# KB_Board_schematic.net
KiCad netlist of a schematic drawn in EAGLE
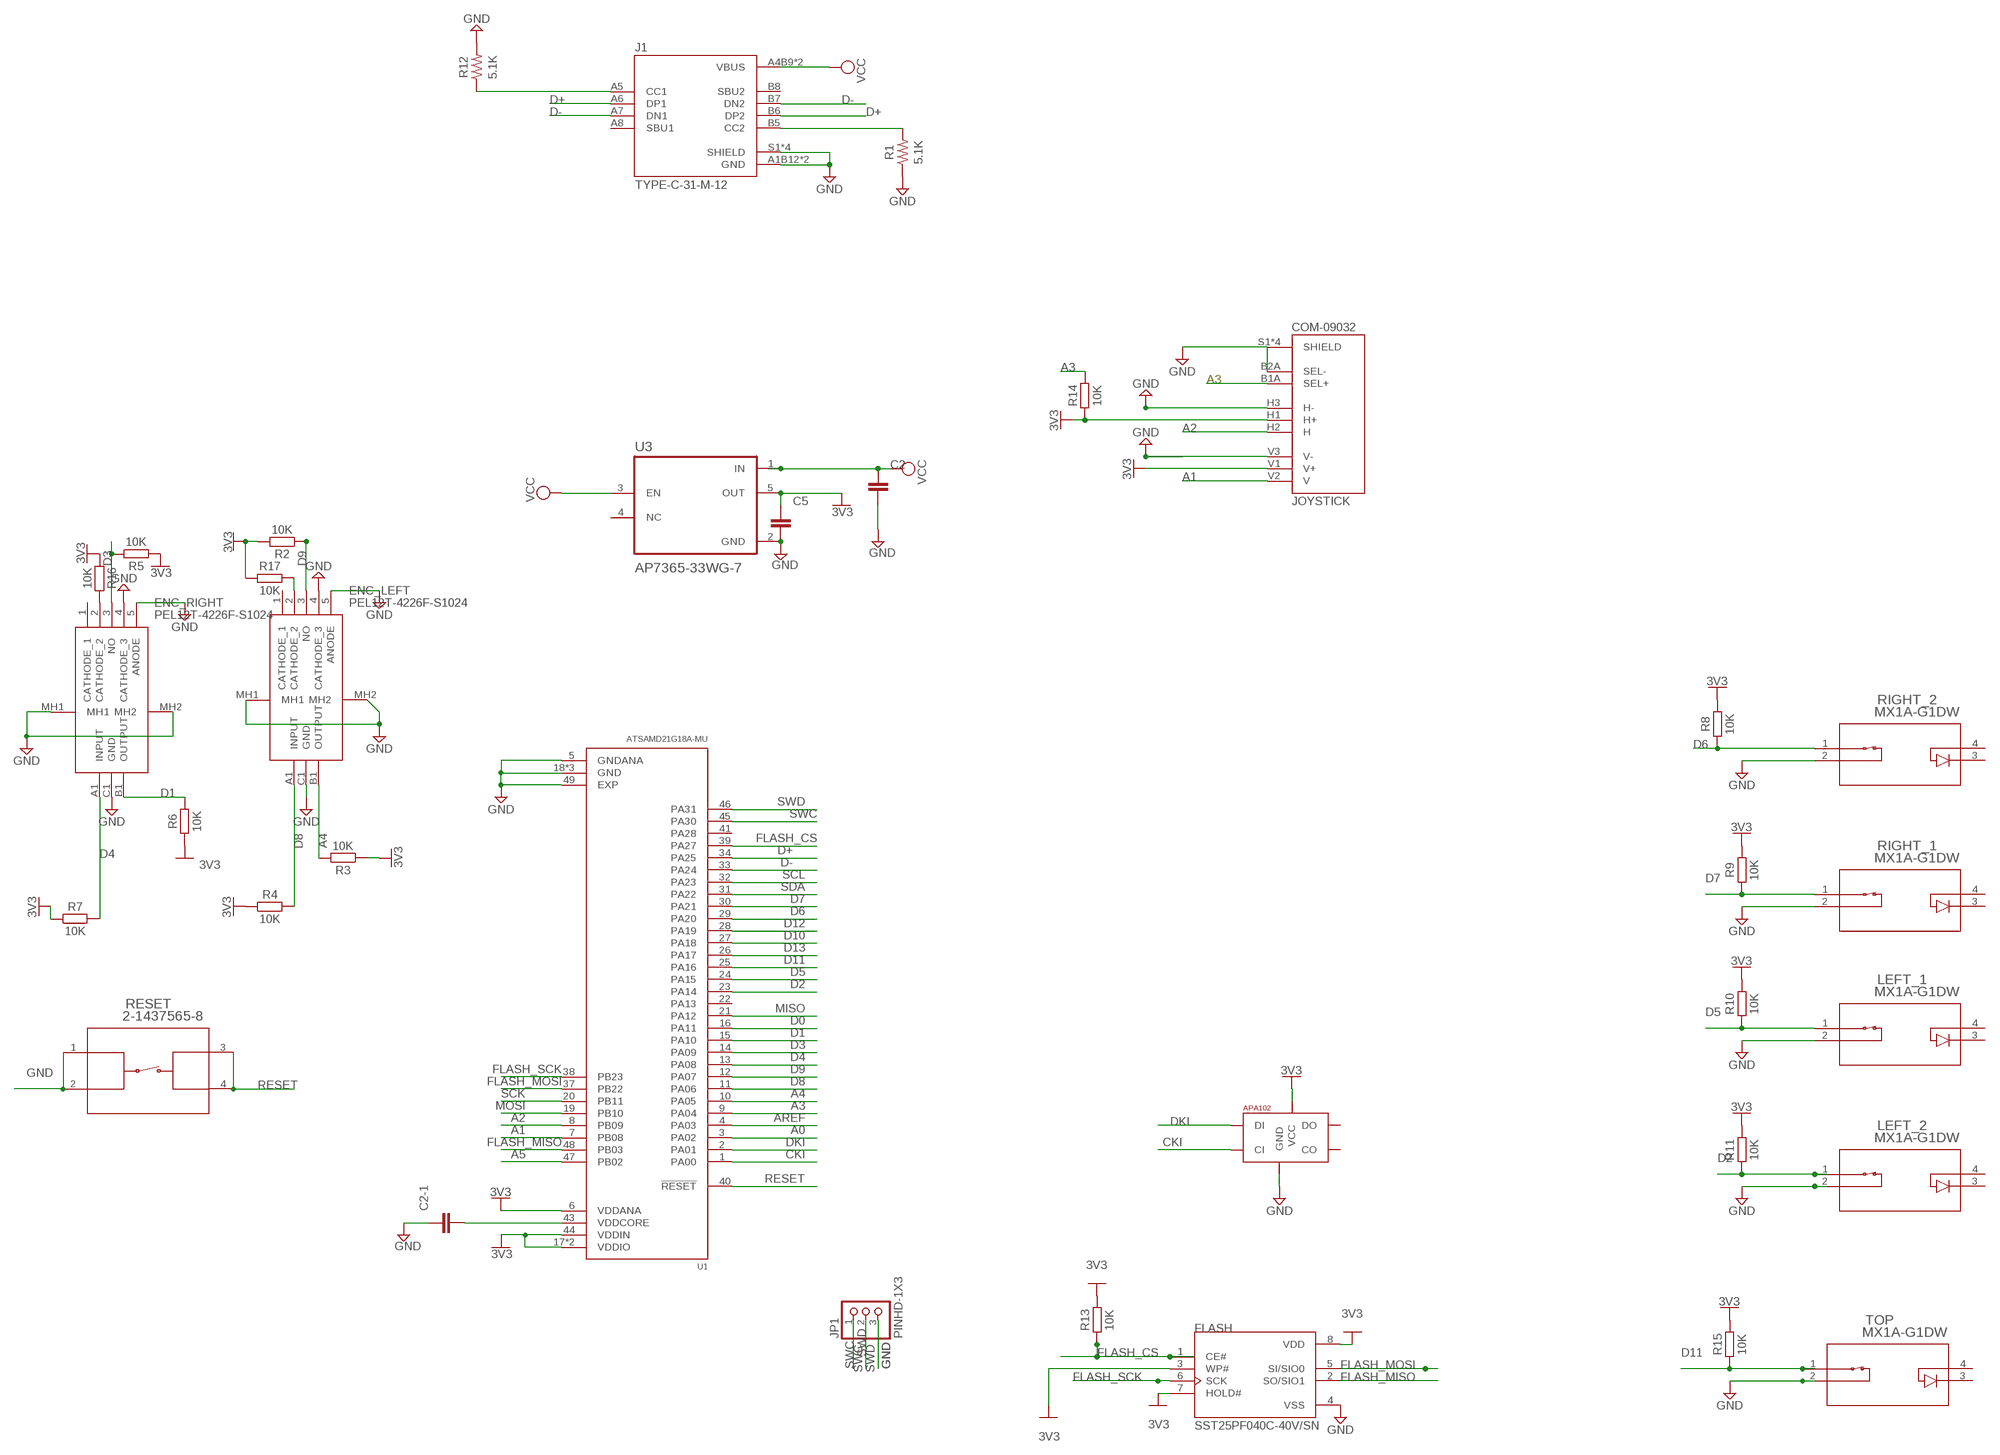
[diagram p0: schematic, sheet 1]

(export (version "E")
  (design (tool "Eeschema 10.0.6"))
  (components
    (comp (ref "C2")
      (value "C_CHIP-0805(2012-METRIC)")
      (footprint "eagle-import:CAPC2012X110")
      (libsource (lib "eagle-import") (part "CCHIP-0805(2012-METRIC)_"))
    )
    (comp (ref "C2-1")
      (value "C_CHIP-0805(2012-METRIC)")
      (footprint "eagle-import:CAPC2012X110")
      (libsource (lib "eagle-import") (part "CCHIP-0805(2012-METRIC)_"))
    )
    (comp (ref "C5")
      (value "C_CHIP-0805(2012-METRIC)")
      (footprint "eagle-import:CAPC2012X110")
      (libsource (lib "eagle-import") (part "CCHIP-0805(2012-METRIC)_"))
    )
    (comp (ref "ENC_LEFT")
      (value "PEL12T-4226F-S1024")
      (footprint "eagle-import:PEL12T4226FS1024")
      (fields (field (name "MOUSER_PART_NUMBER") "652-PEL12T4226FS1024"))
      (libsource (lib "eagle-import") (part "PEL12T-4226F-S1024"))
    )
    (comp (ref "ENC_RIGHT")
      (value "PEL12T-4226F-S1024")
      (footprint "eagle-import:PEL12T4226FS1024")
      (fields (field (name "MOUSER_PART_NUMBER") "652-PEL12T4226FS1024"))
      (libsource (lib "eagle-import") (part "PEL12T-4226F-S1024"))
    )
    (comp (ref "FLASH")
      (value "SST25PF040C-40V/SN")
      (footprint "eagle-import:SOIC8")
      (fields
        (field (name "DIGIKEY_PART_NUMBER") "SST25PF040C-40V/SN-ND")
        (field (name "MANUFACTURER") "Microchip Technology")
        (field (name "CREATED_BY") "PCBLayout.com")
      )
      (libsource (lib "eagle-import") (part "SST25PF040C-40V/SN"))
    )
    (comp (ref "J1")
      (value "TYPE-C-31-M-12")
      (footprint "eagle-import:HRO_TYPE-C-31-M-12")
      (fields (field (name "MANUFACTURER") "HRO Electronics"))
      (libsource (lib "eagle-import") (part "TYPE-C-31-M-12"))
    )
    (comp (ref "JOYSTICK")
      (value "COM-09032")
      (footprint "eagle-import:XDCR_COM-09032")
      (fields (field (name "MANUFACTURER") "SparkFun Electronics"))
      (libsource (lib "eagle-import") (part "COM-09032"))
    )
    (comp (ref "JP1")
      (value "PINHD-1X3")
      (footprint "eagle-import:1X03")
      (libsource (lib "eagle-import") (part "PINHD-1X3"))
    )
    (comp (ref "LEFT_1")
      (value "MX1A-G1DW")
      (footprint "eagle-import:MX1A-G1DW_CHY")
      (fields (field (name "COPYRIGHT") "Copyright (C) 2018 Accelerated Designs. All rights reserved"))
      (libsource (lib "eagle-import") (part "MX1A-G1DW"))
    )
    (comp (ref "LEFT_2")
      (value "MX1A-G1DW")
      (footprint "eagle-import:MX1A-G1DW_CHY")
      (fields (field (name "COPYRIGHT") "Copyright (C) 2018 Accelerated Designs. All rights reserved"))
      (libsource (lib "eagle-import") (part "MX1A-G1DW"))
    )
    (comp (ref "R1")
      (value "5.1K")
      (footprint "eagle-import:RESC1005X40")
      (libsource (lib "eagle-import") (part "R-USCHIP-0402(1005-METRIC)_"))
    )
    (comp (ref "R2")
      (value "10K")
      (footprint "eagle-import:RESC1608X60")
      (libsource (lib "eagle-import") (part "RCHIP-0603(1608-METRIC)_"))
    )
    (comp (ref "R3")
      (value "10K")
      (footprint "eagle-import:RESC1608X60")
      (libsource (lib "eagle-import") (part "RCHIP-0603(1608-METRIC)_"))
    )
    (comp (ref "R4")
      (value "10K")
      (footprint "eagle-import:RESC1608X60")
      (libsource (lib "eagle-import") (part "RCHIP-0603(1608-METRIC)_"))
    )
    (comp (ref "R5")
      (value "10K")
      (footprint "eagle-import:RESC1608X60")
      (libsource (lib "eagle-import") (part "RCHIP-0603(1608-METRIC)_"))
    )
    (comp (ref "R6")
      (value "10K")
      (footprint "eagle-import:RESC1608X60")
      (libsource (lib "eagle-import") (part "RCHIP-0603(1608-METRIC)_"))
    )
    (comp (ref "R7")
      (value "10K")
      (footprint "eagle-import:RESC1608X60")
      (libsource (lib "eagle-import") (part "RCHIP-0603(1608-METRIC)_"))
    )
    (comp (ref "R8")
      (value "10K")
      (footprint "eagle-import:RESC1608X60")
      (libsource (lib "eagle-import") (part "RCHIP-0603(1608-METRIC)_"))
    )
    (comp (ref "R9")
      (value "10K")
      (footprint "eagle-import:RESC1608X60")
      (libsource (lib "eagle-import") (part "RCHIP-0603(1608-METRIC)_"))
    )
    (comp (ref "R10")
      (value "10K")
      (footprint "eagle-import:RESC1608X60")
      (libsource (lib "eagle-import") (part "RCHIP-0603(1608-METRIC)_"))
    )
    (comp (ref "R11")
      (value "10K")
      (footprint "eagle-import:RESC1608X60")
      (libsource (lib "eagle-import") (part "RCHIP-0603(1608-METRIC)_"))
    )
    (comp (ref "R12")
      (value "5.1K")
      (footprint "eagle-import:RESC1005X40")
      (libsource (lib "eagle-import") (part "R-USCHIP-0402(1005-METRIC)_"))
    )
    (comp (ref "R13")
      (value "10K")
      (footprint "eagle-import:RESC1608X60")
      (libsource (lib "eagle-import") (part "RCHIP-0603(1608-METRIC)_"))
    )
    (comp (ref "R14")
      (value "10K")
      (footprint "eagle-import:RESC1608X60")
      (libsource (lib "eagle-import") (part "RCHIP-0603(1608-METRIC)_"))
    )
    (comp (ref "R15")
      (value "10K")
      (footprint "eagle-import:RESC1608X60")
      (libsource (lib "eagle-import") (part "RCHIP-0603(1608-METRIC)_"))
    )
    (comp (ref "R16")
      (value "10K")
      (footprint "eagle-import:RESC1608X60")
      (libsource (lib "eagle-import") (part "RCHIP-0603(1608-METRIC)_"))
    )
    (comp (ref "R17")
      (value "10K")
      (footprint "eagle-import:RESC1608X60")
      (libsource (lib "eagle-import") (part "RCHIP-0603(1608-METRIC)_"))
    )
    (comp (ref "RESET")
      (value "2-1437565-8")
      (footprint "eagle-import:SW4_2-1437565-7")
      (fields (field (name "MANUFACTURER_PART_NUMBER") "FSM2JSMAA"))
      (libsource (lib "eagle-import") (part "2-1437565-8"))
    )
    (comp (ref "RIGHT_1")
      (value "MX1A-G1DW")
      (footprint "eagle-import:MX1A-G1DW_CHY")
      (fields (field (name "COPYRIGHT") "Copyright (C) 2018 Accelerated Designs. All rights reserved"))
      (libsource (lib "eagle-import") (part "MX1A-G1DW"))
    )
    (comp (ref "RIGHT_2")
      (value "MX1A-G1DW")
      (footprint "eagle-import:MX1A-G1DW_CHY")
      (fields (field (name "COPYRIGHT") "Copyright (C) 2018 Accelerated Designs. All rights reserved"))
      (libsource (lib "eagle-import") (part "MX1A-G1DW"))
    )
    (comp (ref "TOP")
      (value "MX1A-G1DW")
      (footprint "eagle-import:MX1A-G1DW_CHY")
      (fields (field (name "COPYRIGHT") "Copyright (C) 2018 Accelerated Designs. All rights reserved"))
      (libsource (lib "eagle-import") (part "MX1A-G1DW"))
    )
    (comp (ref "U$1")
      (value "APA1022020")
      (footprint "eagle-import:APA102_2020")
      (libsource (lib "eagle-import") (part "APA1022020"))
    )
    (comp (ref "U1")
      (value "ATSAMD21G18A-MU")
      (footprint "eagle-import:QFN50P700X700X90-49N")
      (fields (field (name "MF") "Microchip"))
      (libsource (lib "eagle-import") (part "ATSAMD21G18A-MU"))
    )
    (comp (ref "U3")
      (value "AP7365-33WG-7")
      (footprint "eagle-import:SOT95P285X140-5N")
      (fields (field (name "MANUFACTURER") "Diodes Inc."))
      (libsource (lib "eagle-import") (part "AP7365-33WG-7"))
    )
  )
  (nets
    (net (code "1") (name "/A0") (class "Default")
      (node (ref "U1") (pin "3") (pinfunction "PA02_3") (pintype "bidirectional"))
    )
    (net (code "2") (name "/A1") (class "Default")
      (node (ref "JOYSTICK") (pin "V2") (pinfunction "V_V2") (pintype "passive"))
      (node (ref "U1") (pin "7") (pinfunction "PB08_7") (pintype "bidirectional"))
    )
    (net (code "3") (name "/A2") (class "Default")
      (node (ref "JOYSTICK") (pin "H2") (pinfunction "H_H2") (pintype "passive"))
      (node (ref "U1") (pin "8") (pinfunction "PB09_8") (pintype "bidirectional"))
    )
    (net (code "4") (name "/A3") (class "Default")
      (node (ref "JOYSTICK") (pin "B1A") (pinfunction "SEL+_B1A") (pintype "passive"))
      (node (ref "R14") (pin "2") (pinfunction "2_2") (pintype "passive"))
      (node (ref "U1") (pin "9") (pinfunction "PA04_9") (pintype "bidirectional"))
    )
    (net (code "5") (name "/A4") (class "Default")
      (node (ref "ENC_LEFT") (pin "B1") (pinfunction "OUTPUT_B1") (pintype "bidirectional"))
      (node (ref "R3") (pin "2") (pinfunction "2_2") (pintype "passive"))
      (node (ref "U1") (pin "10") (pinfunction "PA05_10") (pintype "bidirectional"))
    )
    (net (code "6") (name "/A5") (class "Default")
      (node (ref "U1") (pin "47") (pinfunction "PB02_47") (pintype "bidirectional"))
    )
    (net (code "7") (name "/AREF") (class "Default")
      (node (ref "U1") (pin "4") (pinfunction "PA03_4") (pintype "bidirectional"))
    )
    (net (code "8") (name "/CKI") (class "Default")
      (node (ref "U$1") (pin "C_IN") (pinfunction "CI_C_IN") (pintype "bidirectional"))
      (node (ref "U1") (pin "1") (pinfunction "PA00_1") (pintype "bidirectional"))
    )
    (net (code "9") (name "/D+") (class "Default")
      (node (ref "J1") (pin "A6") (pinfunction "DP1_A6") (pintype "bidirectional"))
      (node (ref "J1") (pin "B6") (pinfunction "DP2_B6") (pintype "bidirectional"))
      (node (ref "U1") (pin "34") (pinfunction "PA25_34") (pintype "bidirectional"))
    )
    (net (code "10") (name "/D-") (class "Default")
      (node (ref "J1") (pin "A7") (pinfunction "DN1_A7") (pintype "bidirectional"))
      (node (ref "J1") (pin "B7") (pinfunction "DN2_B7") (pintype "bidirectional"))
      (node (ref "U1") (pin "33") (pinfunction "PA24_33") (pintype "bidirectional"))
    )
    (net (code "11") (name "/D0") (class "Default")
      (node (ref "U1") (pin "16") (pinfunction "PA11_16") (pintype "bidirectional"))
    )
    (net (code "12") (name "/D1") (class "Default")
      (node (ref "ENC_RIGHT") (pin "B1") (pinfunction "OUTPUT_B1") (pintype "bidirectional"))
      (node (ref "R6") (pin "2") (pinfunction "2_2") (pintype "passive"))
      (node (ref "U1") (pin "15") (pinfunction "PA10_15") (pintype "bidirectional"))
    )
    (net (code "13") (name "/D2") (class "Default")
      (node (ref "LEFT_2") (pin "1") (pinfunction "1_1") (pintype "passive"))
      (node (ref "R11") (pin "1") (pinfunction "1_1") (pintype "passive"))
      (node (ref "U1") (pin "23") (pinfunction "PA14_23") (pintype "bidirectional"))
    )
    (net (code "14") (name "/D3") (class "Default")
      (node (ref "ENC_RIGHT") (pin "3") (pinfunction "NO_3") (pintype "bidirectional"))
      (node (ref "R5") (pin "1") (pinfunction "1_1") (pintype "passive"))
      (node (ref "U1") (pin "14") (pinfunction "PA09_14") (pintype "bidirectional"))
    )
    (net (code "15") (name "/D4") (class "Default")
      (node (ref "ENC_RIGHT") (pin "A1") (pinfunction "INPUT_A1") (pintype "bidirectional"))
      (node (ref "R7") (pin "2") (pinfunction "2_2") (pintype "passive"))
      (node (ref "U1") (pin "13") (pinfunction "PA08_13") (pintype "bidirectional"))
    )
    (net (code "16") (name "/D5") (class "Default")
      (node (ref "LEFT_1") (pin "1") (pinfunction "1_1") (pintype "passive"))
      (node (ref "R10") (pin "1") (pinfunction "1_1") (pintype "passive"))
      (node (ref "U1") (pin "24") (pinfunction "PA15_24") (pintype "bidirectional"))
    )
    (net (code "17") (name "/D6") (class "Default")
      (node (ref "R8") (pin "1") (pinfunction "1_1") (pintype "passive"))
      (node (ref "RIGHT_2") (pin "1") (pinfunction "1_1") (pintype "passive"))
      (node (ref "U1") (pin "29") (pinfunction "PA20_29") (pintype "bidirectional"))
    )
    (net (code "18") (name "/D7") (class "Default")
      (node (ref "R9") (pin "1") (pinfunction "1_1") (pintype "passive"))
      (node (ref "RIGHT_1") (pin "1") (pinfunction "1_1") (pintype "passive"))
      (node (ref "U1") (pin "30") (pinfunction "PA21_30") (pintype "bidirectional"))
    )
    (net (code "19") (name "/D8") (class "Default")
      (node (ref "ENC_LEFT") (pin "A1") (pinfunction "INPUT_A1") (pintype "bidirectional"))
      (node (ref "R4") (pin "2") (pinfunction "2_2") (pintype "passive"))
      (node (ref "U1") (pin "11") (pinfunction "PA06_11") (pintype "bidirectional"))
    )
    (net (code "20") (name "/D9") (class "Default")
      (node (ref "ENC_LEFT") (pin "3") (pinfunction "NO_3") (pintype "bidirectional"))
      (node (ref "R2") (pin "1") (pinfunction "1_1") (pintype "passive"))
      (node (ref "U1") (pin "12") (pinfunction "PA07_12") (pintype "bidirectional"))
    )
    (net (code "21") (name "/D10") (class "Default")
      (node (ref "U1") (pin "27") (pinfunction "PA18_27") (pintype "bidirectional"))
    )
    (net (code "22") (name "/D11") (class "Default")
      (node (ref "R15") (pin "1") (pinfunction "1_1") (pintype "passive"))
      (node (ref "TOP") (pin "1") (pinfunction "1_1") (pintype "passive"))
      (node (ref "U1") (pin "25") (pinfunction "PA16_25") (pintype "bidirectional"))
    )
    (net (code "23") (name "/D12") (class "Default")
      (node (ref "U1") (pin "28") (pinfunction "PA19_28") (pintype "bidirectional"))
    )
    (net (code "24") (name "/D13") (class "Default")
      (node (ref "U1") (pin "26") (pinfunction "PA17_26") (pintype "bidirectional"))
    )
    (net (code "25") (name "/DKI") (class "Default")
      (node (ref "U$1") (pin "D_IN") (pinfunction "DI_D_IN") (pintype "bidirectional"))
      (node (ref "U1") (pin "2") (pinfunction "PA01_2") (pintype "bidirectional"))
    )
    (net (code "26") (name "/FLASH_CS") (class "Default")
      (node (ref "FLASH") (pin "1") (pinfunction "CE#_1") (pintype "input"))
      (node (ref "R13") (pin "1") (pinfunction "1_1") (pintype "passive"))
      (node (ref "U1") (pin "39") (pinfunction "PA27_39") (pintype "bidirectional"))
    )
    (net (code "27") (name "/FLASH_MISO") (class "Default")
      (node (ref "FLASH") (pin "2") (pinfunction "SO/SIO1_2") (pintype "bidirectional"))
      (node (ref "U1") (pin "48") (pinfunction "PB03_48") (pintype "bidirectional"))
    )
    (net (code "28") (name "/FLASH_MOSI") (class "Default")
      (node (ref "FLASH") (pin "5") (pinfunction "SI/SIO0_5") (pintype "bidirectional"))
      (node (ref "U1") (pin "37") (pinfunction "PB22_37") (pintype "bidirectional"))
    )
    (net (code "29") (name "/FLASH_SCK") (class "Default")
      (node (ref "FLASH") (pin "6") (pinfunction "SCK_6") (pintype "input"))
      (node (ref "U1") (pin "38") (pinfunction "PB23_38") (pintype "bidirectional"))
    )
    (net (code "30") (name "/MISO") (class "Default")
      (node (ref "U1") (pin "21") (pinfunction "PA12_21") (pintype "bidirectional"))
    )
    (net (code "31") (name "/MOSI") (class "Default")
      (node (ref "U1") (pin "19") (pinfunction "PB10_19") (pintype "bidirectional"))
    )
    (net (code "32") (name "/RESET") (class "Default")
      (node (ref "RESET") (pin "3") (pinfunction "3_3") (pintype "passive"))
      (node (ref "RESET") (pin "4") (pinfunction "4_4") (pintype "passive"))
      (node (ref "U1") (pin "40") (pinfunction "~{RESET}_40") (pintype "input"))
    )
    (net (code "33") (name "/SCK") (class "Default")
      (node (ref "U1") (pin "20") (pinfunction "PB11_20") (pintype "bidirectional"))
    )
    (net (code "34") (name "/SCL") (class "Default")
      (node (ref "U1") (pin "32") (pinfunction "PA23_32") (pintype "bidirectional"))
    )
    (net (code "35") (name "/SDA") (class "Default")
      (node (ref "U1") (pin "31") (pinfunction "PA22_31") (pintype "bidirectional"))
    )
    (net (code "36") (name "/SWC") (class "Default")
      (node (ref "JP1") (pin "1") (pinfunction "1_1") (pintype "passive"))
      (node (ref "U1") (pin "45") (pinfunction "PA30_45") (pintype "bidirectional"))
    )
    (net (code "37") (name "/SWD") (class "Default")
      (node (ref "JP1") (pin "2") (pinfunction "2_2") (pintype "passive"))
      (node (ref "U1") (pin "46") (pinfunction "PA31_46") (pintype "bidirectional"))
    )
    (net (code "38") (name "3V3") (class "Default")
      (node (ref "C5") (pin "1") (pinfunction "1_1") (pintype "passive"))
      (node (ref "FLASH") (pin "3") (pinfunction "WP#_3") (pintype "input"))
      (node (ref "FLASH") (pin "7") (pinfunction "HOLD#_7") (pintype "input"))
      (node (ref "FLASH") (pin "8") (pinfunction "VDD_8") (pintype "power_in"))
      (node (ref "JOYSTICK") (pin "H1") (pinfunction "H+_H1") (pintype "passive"))
      (node (ref "JOYSTICK") (pin "V1") (pinfunction "V+_V1") (pintype "passive"))
      (node (ref "R10") (pin "2") (pinfunction "2_2") (pintype "passive"))
      (node (ref "R11") (pin "2") (pinfunction "2_2") (pintype "passive"))
      (node (ref "R13") (pin "2") (pinfunction "2_2") (pintype "passive"))
      (node (ref "R14") (pin "1") (pinfunction "1_1") (pintype "passive"))
      (node (ref "R15") (pin "2") (pinfunction "2_2") (pintype "passive"))
      (node (ref "R16") (pin "2") (pinfunction "2_2") (pintype "passive"))
      (node (ref "R17") (pin "2") (pinfunction "2_2") (pintype "passive"))
      (node (ref "R2") (pin "2") (pinfunction "2_2") (pintype "passive"))
      (node (ref "R3") (pin "1") (pinfunction "1_1") (pintype "passive"))
      (node (ref "R4") (pin "1") (pinfunction "1_1") (pintype "passive"))
      (node (ref "R5") (pin "2") (pinfunction "2_2") (pintype "passive"))
      (node (ref "R6") (pin "1") (pinfunction "1_1") (pintype "passive"))
      (node (ref "R7") (pin "1") (pinfunction "1_1") (pintype "passive"))
      (node (ref "R8") (pin "2") (pinfunction "2_2") (pintype "passive"))
      (node (ref "R9") (pin "2") (pinfunction "2_2") (pintype "passive"))
      (node (ref "U$1") (pin "V_CC") (pinfunction "VCC_V_CC") (pintype "bidirectional"))
      (node (ref "U1") (pin "17") (pinfunction "VDDIO_17") (pintype "power_in"))
      (node (ref "U1") (pin "36") (pinfunction "VDDIO_36") (pintype "power_in"))
      (node (ref "U1") (pin "44") (pinfunction "VDDIN_44") (pintype "power_in"))
      (node (ref "U1") (pin "6") (pinfunction "VDDANA_6") (pintype "power_in"))
      (node (ref "U3") (pin "5") (pinfunction "OUT_5") (pintype "output"))
    )
    (net (code "39") (name "GND") (class "Default")
      (node (ref "C2") (pin "2") (pinfunction "2_2") (pintype "passive"))
      (node (ref "C2-1") (pin "1") (pinfunction "1_1") (pintype "passive"))
      (node (ref "C5") (pin "2") (pinfunction "2_2") (pintype "passive"))
      (node (ref "ENC_LEFT") (pin "4") (pinfunction "CATHODE_3_4") (pintype "bidirectional"))
      (node (ref "ENC_LEFT") (pin "5") (pinfunction "ANODE_5") (pintype "bidirectional"))
      (node (ref "ENC_LEFT") (pin "C1") (pinfunction "GND_C1") (pintype "bidirectional"))
      (node (ref "ENC_LEFT") (pin "MH1") (pinfunction "MH1_MH1") (pintype "bidirectional"))
      (node (ref "ENC_LEFT") (pin "MH2") (pinfunction "MH2_MH2") (pintype "bidirectional"))
      (node (ref "ENC_RIGHT") (pin "4") (pinfunction "CATHODE_3_4") (pintype "bidirectional"))
      (node (ref "ENC_RIGHT") (pin "5") (pinfunction "ANODE_5") (pintype "bidirectional"))
      (node (ref "ENC_RIGHT") (pin "C1") (pinfunction "GND_C1") (pintype "bidirectional"))
      (node (ref "ENC_RIGHT") (pin "MH1") (pinfunction "MH1_MH1") (pintype "bidirectional"))
      (node (ref "ENC_RIGHT") (pin "MH2") (pinfunction "MH2_MH2") (pintype "bidirectional"))
      (node (ref "FLASH") (pin "4") (pinfunction "VSS_4") (pintype "power_in"))
      (node (ref "J1") (pin "A1B12") (pinfunction "GND_A1B12") (pintype "power_in"))
      (node (ref "J1") (pin "B1A12") (pinfunction "GND_B1A12") (pintype "power_in"))
      (node (ref "J1") (pin "S1") (pinfunction "SHIELD_S1") (pintype "passive"))
      (node (ref "J1") (pin "S2") (pinfunction "SHIELD_S2") (pintype "passive"))
      (node (ref "J1") (pin "S3") (pinfunction "SHIELD_S3") (pintype "passive"))
      (node (ref "J1") (pin "S4") (pinfunction "SHIELD_S4") (pintype "passive"))
      (node (ref "JOYSTICK") (pin "B2A") (pinfunction "SEL-_B2A") (pintype "passive"))
      (node (ref "JOYSTICK") (pin "H3") (pinfunction "H-_H3") (pintype "passive"))
      (node (ref "JOYSTICK") (pin "S1") (pinfunction "SHIELD_S1") (pintype "passive"))
      (node (ref "JOYSTICK") (pin "S2") (pinfunction "SHIELD_S2") (pintype "passive"))
      (node (ref "JOYSTICK") (pin "S3") (pinfunction "SHIELD_S3") (pintype "passive"))
      (node (ref "JOYSTICK") (pin "S4") (pinfunction "SHIELD_S4") (pintype "passive"))
      (node (ref "JOYSTICK") (pin "V3") (pinfunction "V-_V3") (pintype "passive"))
      (node (ref "JP1") (pin "3") (pinfunction "3_3") (pintype "passive"))
      (node (ref "LEFT_1") (pin "2") (pinfunction "2_2") (pintype "passive"))
      (node (ref "LEFT_2") (pin "2") (pinfunction "2_2") (pintype "passive"))
      (node (ref "R1") (pin "1") (pinfunction "1_1") (pintype "passive"))
      (node (ref "R12") (pin "2") (pinfunction "2_2") (pintype "passive"))
      (node (ref "RESET") (pin "1") (pinfunction "1_1") (pintype "passive"))
      (node (ref "RESET") (pin "2") (pinfunction "2_2") (pintype "passive"))
      (node (ref "RIGHT_1") (pin "2") (pinfunction "2_2") (pintype "passive"))
      (node (ref "RIGHT_2") (pin "2") (pinfunction "2_2") (pintype "passive"))
      (node (ref "TOP") (pin "2") (pinfunction "2_2") (pintype "passive"))
      (node (ref "U$1") (pin "GND") (pinfunction "GND_GND") (pintype "bidirectional"))
      (node (ref "U1") (pin "18") (pinfunction "GND_18") (pintype "power_in"))
      (node (ref "U1") (pin "35") (pinfunction "GND_35") (pintype "power_in"))
      (node (ref "U1") (pin "42") (pinfunction "GND_42") (pintype "power_in"))
      (node (ref "U1") (pin "49") (pinfunction "EXP_49") (pintype "power_in"))
      (node (ref "U1") (pin "5") (pinfunction "GNDANA_5") (pintype "power_in"))
      (node (ref "U3") (pin "2") (pinfunction "GND_2") (pintype "power_in"))
    )
    (net (code "40") (name "Net-(ENC_LEFT-CATHODE_2)") (class "Default")
      (node (ref "ENC_LEFT") (pin "2") (pinfunction "CATHODE_2_2") (pintype "bidirectional"))
      (node (ref "R17") (pin "1") (pinfunction "1_1") (pintype "passive"))
    )
    (net (code "41") (name "Net-(ENC_RIGHT-CATHODE_2)") (class "Default")
      (node (ref "ENC_RIGHT") (pin "2") (pinfunction "CATHODE_2_2") (pintype "bidirectional"))
      (node (ref "R16") (pin "1") (pinfunction "1_1") (pintype "passive"))
    )
    (net (code "42") (name "Net-(J1-CC1)") (class "Default")
      (node (ref "J1") (pin "A5") (pinfunction "CC1_A5") (pintype "bidirectional"))
      (node (ref "R12") (pin "1") (pinfunction "1_1") (pintype "passive"))
    )
    (net (code "43") (name "Net-(J1-CC2)") (class "Default")
      (node (ref "J1") (pin "B5") (pinfunction "CC2_B5") (pintype "bidirectional"))
      (node (ref "R1") (pin "2") (pinfunction "2_2") (pintype "passive"))
    )
    (net (code "44") (name "Net-(U1-VDDCORE)") (class "Default")
      (node (ref "C2-1") (pin "2") (pinfunction "2_2") (pintype "passive"))
      (node (ref "U1") (pin "43") (pinfunction "VDDCORE_43") (pintype "power_in"))
    )
    (net (code "45") (name "VCC") (class "Default")
      (node (ref "C2") (pin "1") (pinfunction "1_1") (pintype "passive"))
      (node (ref "J1") (pin "A4B9") (pinfunction "VBUS_A4B9") (pintype "power_in"))
      (node (ref "J1") (pin "B4A9") (pinfunction "VBUS_B4A9") (pintype "power_in"))
      (node (ref "U3") (pin "1") (pinfunction "IN_1") (pintype "power_in"))
      (node (ref "U3") (pin "3") (pinfunction "EN_3") (pintype "input"))
    )
    (net (code "46") (name "unconnected-(ENC_LEFT-CATHODE_1-Pad1)") (class "Default")
      (node (ref "ENC_LEFT") (pin "1") (pinfunction "CATHODE_1_1") (pintype "bidirectional"))
    )
    (net (code "47") (name "unconnected-(ENC_RIGHT-CATHODE_1-Pad1)") (class "Default")
      (node (ref "ENC_RIGHT") (pin "1") (pinfunction "CATHODE_1_1") (pintype "bidirectional"))
    )
    (net (code "48") (name "unconnected-(J1-SBU1-PadA8)") (class "Default")
      (node (ref "J1") (pin "A8") (pinfunction "SBU1_A8") (pintype "bidirectional"))
    )
    (net (code "49") (name "unconnected-(J1-SBU2-PadB8)") (class "Default")
      (node (ref "J1") (pin "B8") (pinfunction "SBU2_B8") (pintype "bidirectional"))
    )
    (net (code "50") (name "unconnected-(LEFT_1-Pad3)") (class "Default")
      (node (ref "LEFT_1") (pin "3") (pinfunction "3_3") (pintype "passive"))
    )
    (net (code "51") (name "unconnected-(LEFT_1-Pad4)") (class "Default")
      (node (ref "LEFT_1") (pin "4") (pinfunction "4_4") (pintype "passive"))
    )
    (net (code "52") (name "unconnected-(LEFT_2-Pad3)") (class "Default")
      (node (ref "LEFT_2") (pin "3") (pinfunction "3_3") (pintype "passive"))
    )
    (net (code "53") (name "unconnected-(LEFT_2-Pad4)") (class "Default")
      (node (ref "LEFT_2") (pin "4") (pinfunction "4_4") (pintype "passive"))
    )
    (net (code "54") (name "unconnected-(RIGHT_1-Pad3)") (class "Default")
      (node (ref "RIGHT_1") (pin "3") (pinfunction "3_3") (pintype "passive"))
    )
    (net (code "55") (name "unconnected-(RIGHT_1-Pad4)") (class "Default")
      (node (ref "RIGHT_1") (pin "4") (pinfunction "4_4") (pintype "passive"))
    )
    (net (code "56") (name "unconnected-(RIGHT_2-Pad3)") (class "Default")
      (node (ref "RIGHT_2") (pin "3") (pinfunction "3_3") (pintype "passive"))
    )
    (net (code "57") (name "unconnected-(RIGHT_2-Pad4)") (class "Default")
      (node (ref "RIGHT_2") (pin "4") (pinfunction "4_4") (pintype "passive"))
    )
    (net (code "58") (name "unconnected-(TOP-Pad3)") (class "Default")
      (node (ref "TOP") (pin "3") (pinfunction "3_3") (pintype "passive"))
    )
    (net (code "59") (name "unconnected-(TOP-Pad4)") (class "Default")
      (node (ref "TOP") (pin "4") (pinfunction "4_4") (pintype "passive"))
    )
    (net (code "60") (name "unconnected-(U$1-CO-PadCL_OUT)") (class "Default")
      (node (ref "U$1") (pin "CL_OUT") (pinfunction "CO_CL_OUT") (pintype "bidirectional"))
    )
    (net (code "61") (name "unconnected-(U$1-DO-PadD_OUT)") (class "Default")
      (node (ref "U$1") (pin "D_OUT") (pinfunction "DO_D_OUT") (pintype "bidirectional"))
    )
    (net (code "62") (name "unconnected-(U1-PA13-Pad22)") (class "Default")
      (node (ref "U1") (pin "22") (pinfunction "PA13_22") (pintype "bidirectional"))
    )
    (net (code "63") (name "unconnected-(U1-PA28-Pad41)") (class "Default")
      (node (ref "U1") (pin "41") (pinfunction "PA28_41") (pintype "bidirectional"))
    )
    (net (code "64") (name "unconnected-(U3-NC-Pad4)") (class "Default")
      (node (ref "U3") (pin "4") (pinfunction "NC_4") (pintype "bidirectional"))
    )
  )
)
